# USB.net
KiCad netlist of a schematic drawn in EasyEDA Pro
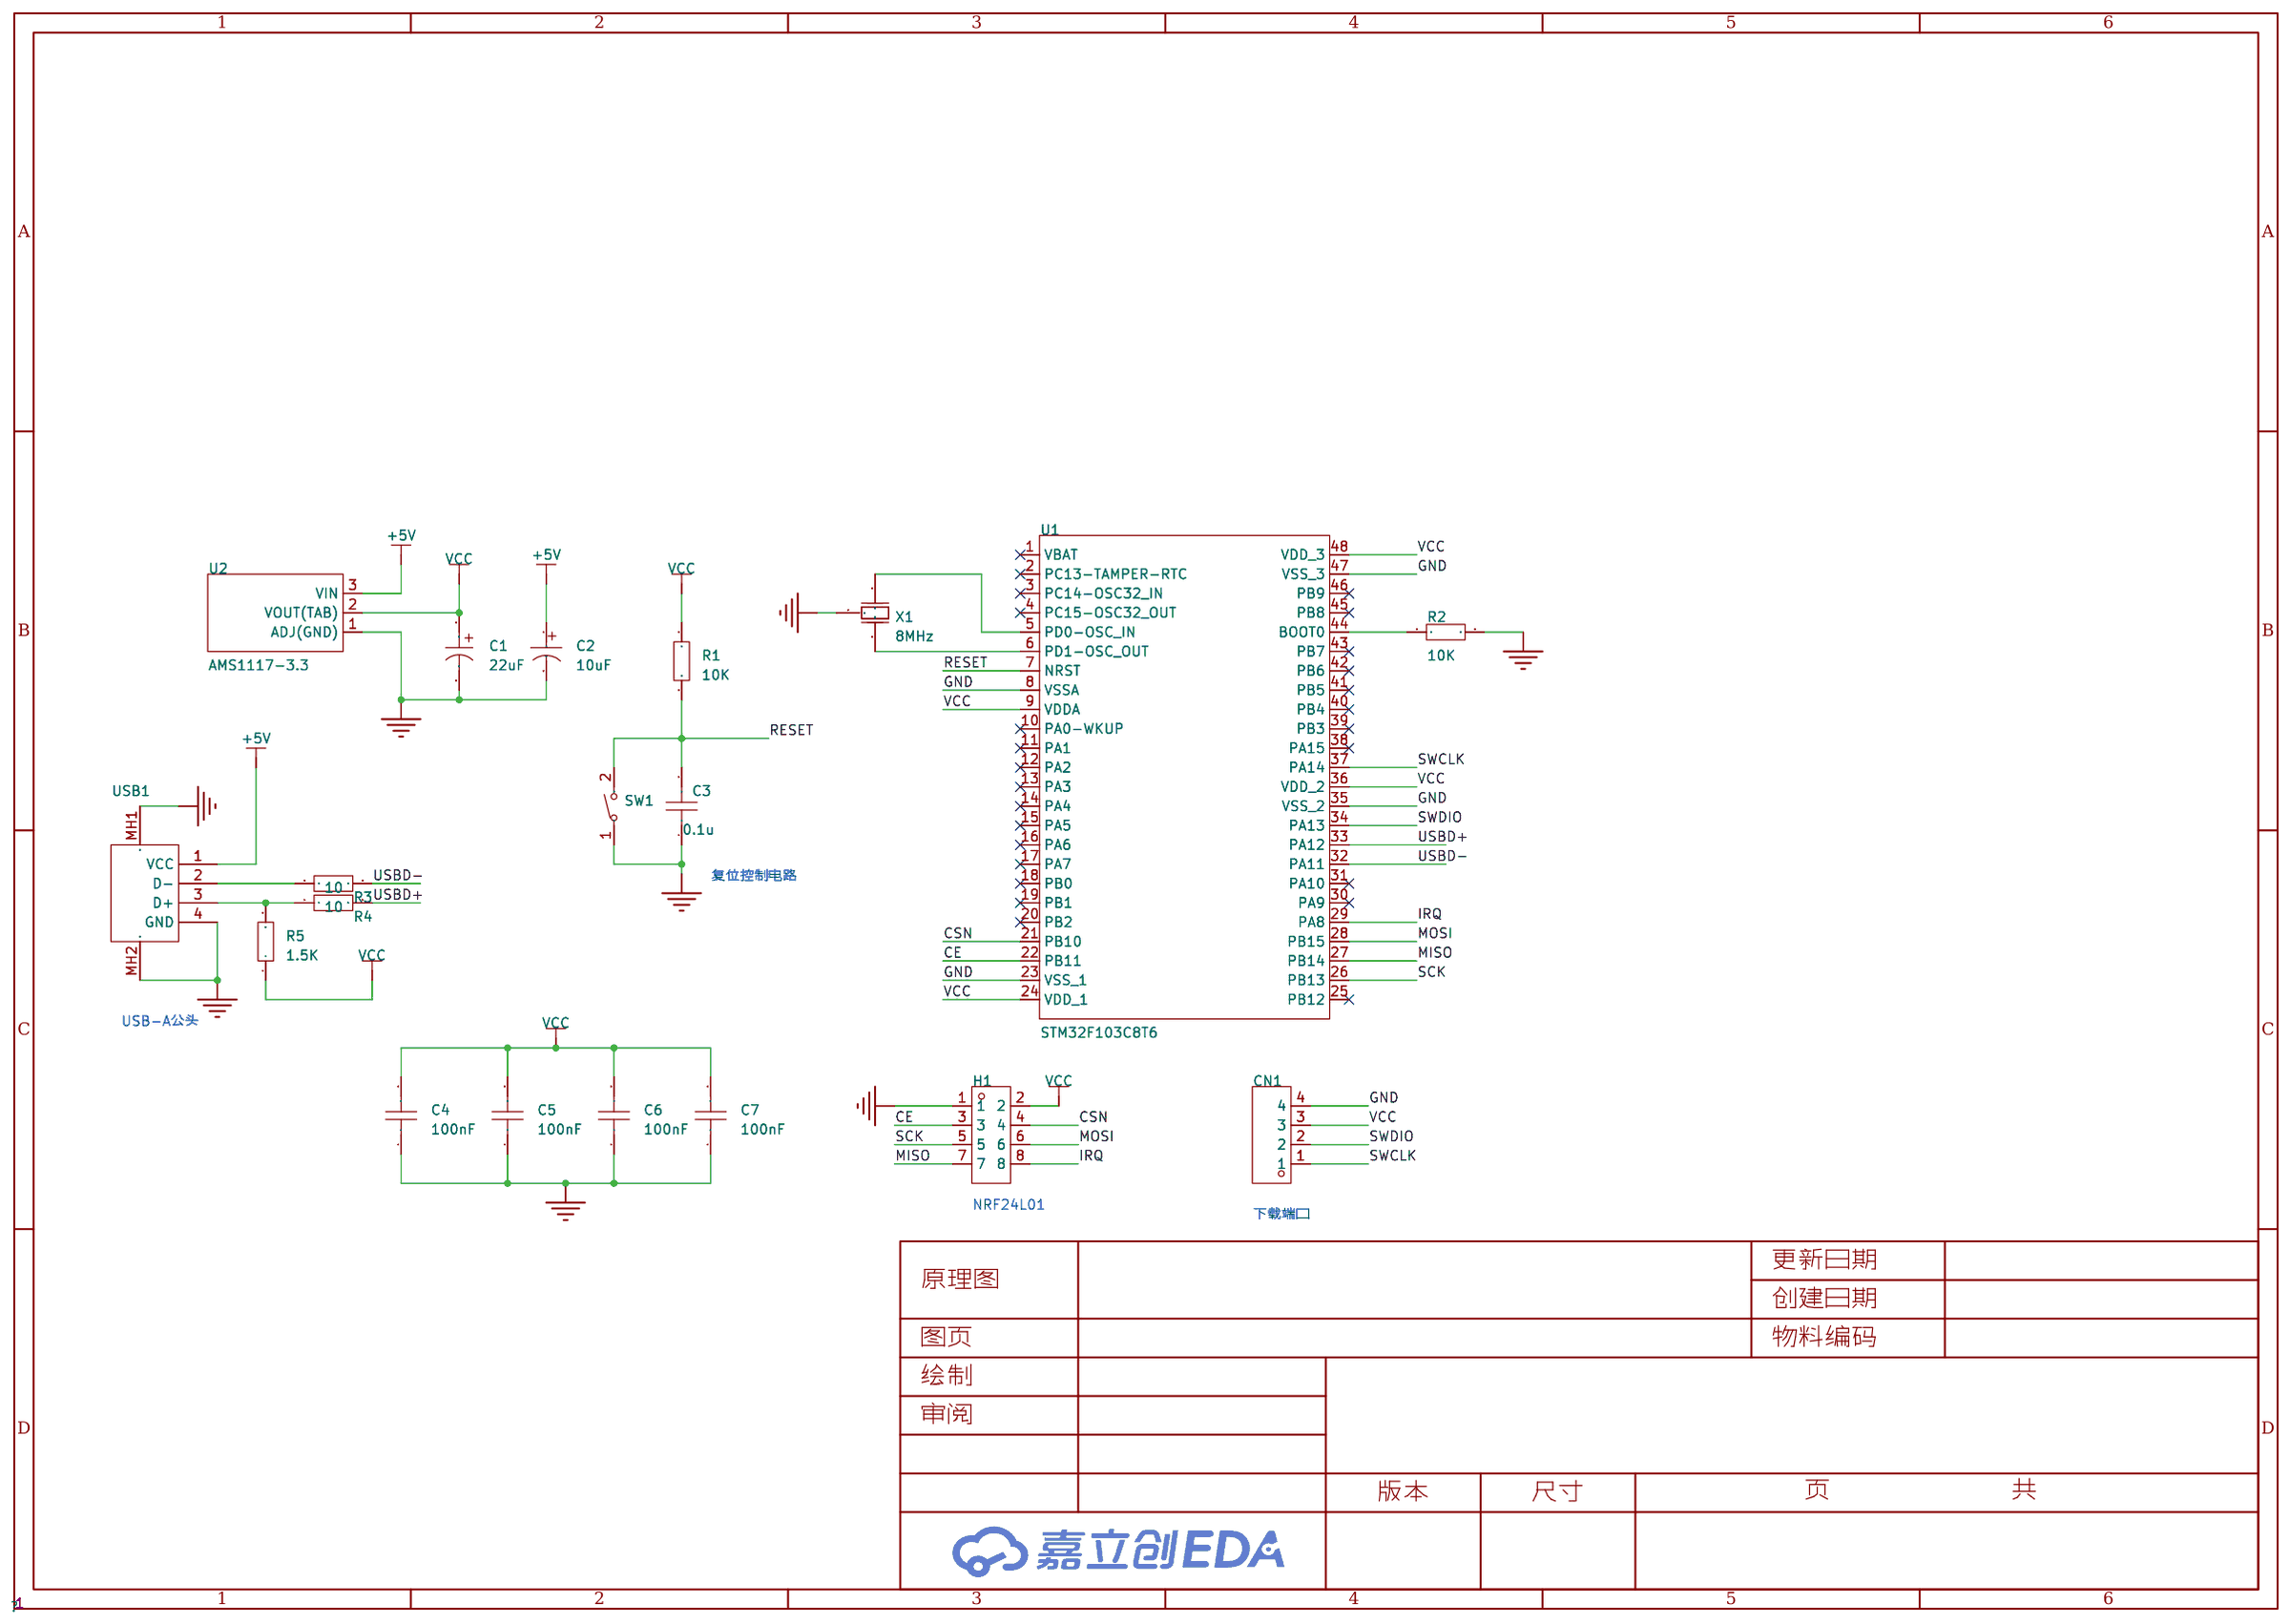
[diagram p0: schematic sheet]

(export (version "E")
  (design (tool "Eeschema 10.0.6"))
  (components
    (comp (ref "C1")
      (value "22uF")
      (footprint "easyedapro:CAP-SMD_BD5.0-L5.3-W5.3-LS6.0-FD")
      (description "容值:22uF;精度:±20%;额定电压:25V;纹波电流:25mA@120Hz;")
      (fields (field (name "Manufacturer Part") "CS1E220M-CRD54") (field (name "Manufacturer") "ROQANG(容强)"))
      (libsource (lib "easyedapro") (part "CS1E220M-CRD54_C3001207"))
    )
    (comp (ref "C2")
      (value "10uF")
      (footprint "easyedapro:CAP-SMD_BD4.0-L4.3-W4.3-FD")
      (description "容值:10uF;精度:±20%;额定电压:35V;纹波电流:15mA@120Hz;等效串联电阻(ESR):-;")
      (fields (field (name "Manufacturer Part") "RVT1V100M0405") (field (name "Manufacturer") "ROQANG(容强)"))
      (libsource (lib "easyedapro") (part "RVT1V100M0405-C72485"))
    )
    (comp (ref "C3")
      (value "0.1u")
      (footprint "easyedapro:C0603")
      (libsource (lib "easyedapro") (part "CapAcitance"))
    )
    (comp (ref "C4")
      (value "100nF")
      (footprint "easyedapro:C0603")
      (libsource (lib "easyedapro") (part "CapAcitance"))
    )
    (comp (ref "C5")
      (value "100nF")
      (footprint "easyedapro:C0603")
      (libsource (lib "easyedapro") (part "CapAcitance"))
    )
    (comp (ref "C6")
      (value "100nF")
      (footprint "easyedapro:C0603")
      (libsource (lib "easyedapro") (part "CapAcitance"))
    )
    (comp (ref "C7")
      (value "100nF")
      (footprint "easyedapro:C0603")
      (libsource (lib "easyedapro") (part "CapAcitance"))
    )
    (comp (ref "CN1")
      (value "HC-ZH1.5-4AW")
      (footprint "easyedapro:CONN-TH_4P-P1.50_HCTL_HC-ZH1.5-4AW")
      (fields (field (name "Manufacturer") "HCTL(华灿天禄)"))
      (libsource (lib "easyedapro") (part "HC-ZH1.5-4AW"))
    )
    (comp (ref "H1")
      (value "PM254V-12-08-H85")
      (footprint "easyedapro:HDR-TH_8P-P2.54-V-F-R2-C4-S2.54")
      (fields (field (name "Manufacturer") "XFCN(兴飞)"))
      (libsource (lib "easyedapro") (part "PM254V-12-08-H85_C2834799"))
    )
    (comp (ref "R1") (value "10K") (footprint "easyedapro:R0603") (libsource (lib "easyedapro") (part "电阻")))
    (comp (ref "R2") (value "10K") (footprint "easyedapro:R0603") (libsource (lib "easyedapro") (part "电阻")))
    (comp (ref "R3") (value "10") (footprint "easyedapro:R0603") (libsource (lib "easyedapro") (part "电阻")))
    (comp (ref "R4") (value "10") (footprint "easyedapro:R0603") (libsource (lib "easyedapro") (part "电阻")))
    (comp (ref "R5") (value "1.5K") (footprint "easyedapro:R0603") (libsource (lib "easyedapro") (part "电阻")))
    (comp (ref "SW1")
      (value "GT-TC060A-H025-L1S")
      (footprint "easyedapro:SW-SMD_L6.1-W3.5-LS8.0")
      (description "电路结构:单刀单掷;作用力:1.6N;安装方式:立贴;带支架:不带;触点电流:50mA;额定电压(AC):12V;额定电压(DC):12V;绝缘电阻:100MΩ;带灯:无;机械寿命:10万次;")
      (fields (field (name "Manufacturer") "G-Switch(品赞)"))
      (libsource (lib "easyedapro") (part "GT-TC060A-H025-L1S"))
    )
    (comp (ref "U1")
      (value "STM32F103C8T6")
      (footprint "easyedapro:LQFP-48_L7.0-W7.0-P0.50-LS9.0-BL")
      (description "CPU内核:ARM-M3;CPU最大主频:72MHz;应用领域:-;")
      (fields (field (name "Manufacturer") "ST(意法半导体)"))
      (libsource (lib "easyedapro") (part "STM32F103C8T6"))
    )
    (comp (ref "U2")
      (value "AMS1117-3.3")
      (footprint "easyedapro:SOT-89_L4.5-W2.5-P1.50-LS4.2-BR")
      (description "输出类型:固定;工作电压:18V;输出电压:3.3V;输出电流:1A;电源纹波抑制比(PSRR):60dB@(120Hz);输出极性:正极;")
      (fields (field (name "Manufacturer") "UMW(友台半导体)"))
      (libsource (lib "easyedapro") (part "AMS1117-3.3_C347256"))
    )
    (comp (ref "USB1")
      (value "AM90")
      (footprint "easyedapro:USB-AM-TH_AM90")
      (description "连接器类型:Type-A;标准:USB 2.0;公母:公;安装方式:弯插;触点数量:4P;端口数量:1;额定电流 - 电源:1.5A;工作温度范围:-25°C~+85°C;")
      (fields (field (name "Manufacturer") "SHOU HAN(首韩)"))
      (libsource (lib "easyedapro") (part "AM90"))
    )
    (comp (ref "X1")
      (value "8MHz")
      (footprint "easyedapro:OSC-SMD_3P-L3.2-W1.3-P1.2-L")
      (description "频率:8MHz;内置负载电容:33pF;谐振阻抗:40Ω;")
      (fields
        (field (name "Manufacturer Part") "CSTNE8M00G55A000R0")
        (field (name "Manufacturer") "muRata(村田)")
      )
      (libsource (lib "easyedapro") (part "CSTNE8M00G55A000R0"))
    )
  )
  (nets
    (net (code "1") (name "+5V") (class "Default")
      (node (ref "C2") (pin "1") (pinfunction "1_1") (pintype "input"))
      (node (ref "U2") (pin "3") (pinfunction "VIN_3") (pintype "unspecified"))
      (node (ref "USB1") (pin "1") (pinfunction "VCC_1") (pintype "input"))
    )
    (net (code "2") (name "/CE") (class "Default")
      (node (ref "H1") (pin "3") (pinfunction "3_3") (pintype "unspecified"))
      (node (ref "U1") (pin "22") (pinfunction "PB11_22") (pintype "unspecified"))
    )
    (net (code "3") (name "/CSN") (class "Default")
      (node (ref "H1") (pin "4") (pinfunction "4_4") (pintype "unspecified"))
      (node (ref "U1") (pin "21") (pinfunction "PB10_21") (pintype "unspecified"))
    )
    (net (code "4") (name "/IRQ") (class "Default")
      (node (ref "H1") (pin "8") (pinfunction "8_8") (pintype "unspecified"))
      (node (ref "U1") (pin "29") (pinfunction "PA8_29") (pintype "unspecified"))
    )
    (net (code "5") (name "/MISO") (class "Default")
      (node (ref "H1") (pin "7") (pinfunction "7_7") (pintype "unspecified"))
      (node (ref "U1") (pin "27") (pinfunction "PB14_27") (pintype "unspecified"))
    )
    (net (code "6") (name "/MOSI") (class "Default")
      (node (ref "H1") (pin "6") (pinfunction "6_6") (pintype "unspecified"))
      (node (ref "U1") (pin "28") (pinfunction "PB15_28") (pintype "unspecified"))
    )
    (net (code "7") (name "/RESET") (class "Default")
      (node (ref "C3") (pin "2") (pinfunction "2_2") (pintype "input"))
      (node (ref "R1") (pin "2") (pinfunction "2_2") (pintype "input"))
      (node (ref "SW1") (pin "2") (pinfunction "2_2") (pintype "unspecified"))
      (node (ref "U1") (pin "7") (pinfunction "NRST_7") (pintype "unspecified"))
    )
    (net (code "8") (name "/SCK") (class "Default")
      (node (ref "H1") (pin "5") (pinfunction "5_5") (pintype "unspecified"))
      (node (ref "U1") (pin "26") (pinfunction "PB13_26") (pintype "unspecified"))
    )
    (net (code "9") (name "/SWCLK") (class "Default")
      (node (ref "CN1") (pin "1") (pinfunction "1_1") (pintype "unspecified"))
      (node (ref "U1") (pin "37") (pinfunction "PA14_37") (pintype "unspecified"))
    )
    (net (code "10") (name "/SWDIO") (class "Default")
      (node (ref "CN1") (pin "2") (pinfunction "2_2") (pintype "unspecified"))
      (node (ref "U1") (pin "34") (pinfunction "PA13_34") (pintype "unspecified"))
    )
    (net (code "11") (name "/USBD+") (class "Default")
      (node (ref "R4") (pin "2") (pinfunction "2_2") (pintype "input"))
      (node (ref "U1") (pin "33") (pinfunction "PA12_33") (pintype "unspecified"))
    )
    (net (code "12") (name "/USBD-") (class "Default")
      (node (ref "R3") (pin "2") (pinfunction "2_2") (pintype "input"))
      (node (ref "U1") (pin "32") (pinfunction "PA11_32") (pintype "unspecified"))
    )
    (net (code "13") (name "GND") (class "Default")
      (node (ref "C1") (pin "2") (pinfunction "2_2") (pintype "input"))
      (node (ref "C2") (pin "2") (pinfunction "2_2") (pintype "input"))
      (node (ref "C3") (pin "1") (pinfunction "1_1") (pintype "input"))
      (node (ref "C4") (pin "1") (pinfunction "1_1") (pintype "input"))
      (node (ref "C5") (pin "1") (pinfunction "1_1") (pintype "input"))
      (node (ref "C6") (pin "1") (pinfunction "1_1") (pintype "input"))
      (node (ref "C7") (pin "1") (pinfunction "1_1") (pintype "input"))
      (node (ref "CN1") (pin "4") (pinfunction "4_4") (pintype "unspecified"))
      (node (ref "H1") (pin "1") (pinfunction "1_1") (pintype "unspecified"))
      (node (ref "R2") (pin "2") (pinfunction "2_2") (pintype "input"))
      (node (ref "SW1") (pin "1") (pinfunction "1_1") (pintype "unspecified"))
      (node (ref "U1") (pin "23") (pinfunction "VSS_1_23") (pintype "unspecified"))
      (node (ref "U1") (pin "35") (pinfunction "VSS_2_35") (pintype "unspecified"))
      (node (ref "U1") (pin "47") (pinfunction "VSS_3_47") (pintype "unspecified"))
      (node (ref "U1") (pin "8") (pinfunction "VSSA_8") (pintype "unspecified"))
      (node (ref "U2") (pin "1") (pinfunction "ADJ(GND)_1") (pintype "unspecified"))
      (node (ref "USB1") (pin "4") (pinfunction "GND_4") (pintype "input"))
      (node (ref "USB1") (pin "MH1") (pinfunction "MH1_MH1") (pintype "unspecified"))
      (node (ref "USB1") (pin "MH2") (pinfunction "MH2_MH2") (pintype "unspecified"))
      (node (ref "X1") (pin "2") (pinfunction "GND_2") (pintype "input"))
    )
    (net (code "14") (name "Net-(U1-BOOT0)") (class "Default")
      (node (ref "R2") (pin "1") (pinfunction "1_1") (pintype "input"))
      (node (ref "U1") (pin "44") (pinfunction "BOOT0_44") (pintype "unspecified"))
    )
    (net (code "15") (name "Net-(U1-PD0-OSC_IN)") (class "Default")
      (node (ref "U1") (pin "5") (pinfunction "PD0-OSC_IN_5") (pintype "unspecified"))
      (node (ref "X1") (pin "3") (pinfunction "OSC2_3") (pintype "input"))
    )
    (net (code "16") (name "Net-(U1-PD1-OSC_OUT)") (class "Default")
      (node (ref "U1") (pin "6") (pinfunction "PD1-OSC_OUT_6") (pintype "unspecified"))
      (node (ref "X1") (pin "1") (pinfunction "OSC1_1") (pintype "input"))
    )
    (net (code "17") (name "Net-(USB1-D+)") (class "Default")
      (node (ref "R4") (pin "1") (pinfunction "1_1") (pintype "input"))
      (node (ref "R5") (pin "2") (pinfunction "2_2") (pintype "input"))
      (node (ref "USB1") (pin "3") (pinfunction "D+_3") (pintype "input"))
    )
    (net (code "18") (name "Net-(USB1-D-)") (class "Default")
      (node (ref "R3") (pin "1") (pinfunction "1_1") (pintype "input"))
      (node (ref "USB1") (pin "2") (pinfunction "D-_2") (pintype "input"))
    )
    (net (code "19") (name "VCC") (class "Default")
      (node (ref "C1") (pin "1") (pinfunction "1_1") (pintype "input"))
      (node (ref "C4") (pin "2") (pinfunction "2_2") (pintype "input"))
      (node (ref "C5") (pin "2") (pinfunction "2_2") (pintype "input"))
      (node (ref "C6") (pin "2") (pinfunction "2_2") (pintype "input"))
      (node (ref "C7") (pin "2") (pinfunction "2_2") (pintype "input"))
      (node (ref "CN1") (pin "3") (pinfunction "3_3") (pintype "unspecified"))
      (node (ref "H1") (pin "2") (pinfunction "2_2") (pintype "unspecified"))
      (node (ref "R1") (pin "1") (pinfunction "1_1") (pintype "input"))
      (node (ref "R5") (pin "1") (pinfunction "1_1") (pintype "input"))
      (node (ref "U1") (pin "24") (pinfunction "VDD_1_24") (pintype "unspecified"))
      (node (ref "U1") (pin "36") (pinfunction "VDD_2_36") (pintype "unspecified"))
      (node (ref "U1") (pin "48") (pinfunction "VDD_3_48") (pintype "unspecified"))
      (node (ref "U1") (pin "9") (pinfunction "VDDA_9") (pintype "unspecified"))
      (node (ref "U2") (pin "2") (pinfunction "VOUT(TAB)_2") (pintype "unspecified"))
    )
    (net (code "20") (name "unconnected-(U1-PA0-WKUP-Pad10)") (class "Default")
      (node (ref "U1") (pin "10") (pinfunction "PA0-WKUP_10") (pintype "unspecified+no_connect"))
    )
    (net (code "21") (name "unconnected-(U1-PA1-Pad11)") (class "Default")
      (node (ref "U1") (pin "11") (pinfunction "PA1_11") (pintype "unspecified+no_connect"))
    )
    (net (code "22") (name "unconnected-(U1-PA2-Pad12)") (class "Default")
      (node (ref "U1") (pin "12") (pinfunction "PA2_12") (pintype "unspecified+no_connect"))
    )
    (net (code "23") (name "unconnected-(U1-PA3-Pad13)") (class "Default")
      (node (ref "U1") (pin "13") (pinfunction "PA3_13") (pintype "unspecified+no_connect"))
    )
    (net (code "24") (name "unconnected-(U1-PA4-Pad14)") (class "Default")
      (node (ref "U1") (pin "14") (pinfunction "PA4_14") (pintype "unspecified+no_connect"))
    )
    (net (code "25") (name "unconnected-(U1-PA5-Pad15)") (class "Default")
      (node (ref "U1") (pin "15") (pinfunction "PA5_15") (pintype "unspecified+no_connect"))
    )
    (net (code "26") (name "unconnected-(U1-PA6-Pad16)") (class "Default")
      (node (ref "U1") (pin "16") (pinfunction "PA6_16") (pintype "unspecified+no_connect"))
    )
    (net (code "27") (name "unconnected-(U1-PA7-Pad17)") (class "Default")
      (node (ref "U1") (pin "17") (pinfunction "PA7_17") (pintype "unspecified+no_connect"))
    )
    (net (code "28") (name "unconnected-(U1-PA9-Pad30)") (class "Default")
      (node (ref "U1") (pin "30") (pinfunction "PA9_30") (pintype "unspecified+no_connect"))
    )
    (net (code "29") (name "unconnected-(U1-PA10-Pad31)") (class "Default")
      (node (ref "U1") (pin "31") (pinfunction "PA10_31") (pintype "unspecified+no_connect"))
    )
    (net (code "30") (name "unconnected-(U1-PA15-Pad38)") (class "Default")
      (node (ref "U1") (pin "38") (pinfunction "PA15_38") (pintype "unspecified+no_connect"))
    )
    (net (code "31") (name "unconnected-(U1-PB0-Pad18)") (class "Default")
      (node (ref "U1") (pin "18") (pinfunction "PB0_18") (pintype "unspecified+no_connect"))
    )
    (net (code "32") (name "unconnected-(U1-PB1-Pad19)") (class "Default")
      (node (ref "U1") (pin "19") (pinfunction "PB1_19") (pintype "unspecified+no_connect"))
    )
    (net (code "33") (name "unconnected-(U1-PB2-Pad20)") (class "Default")
      (node (ref "U1") (pin "20") (pinfunction "PB2_20") (pintype "unspecified+no_connect"))
    )
    (net (code "34") (name "unconnected-(U1-PB3-Pad39)") (class "Default")
      (node (ref "U1") (pin "39") (pinfunction "PB3_39") (pintype "unspecified+no_connect"))
    )
    (net (code "35") (name "unconnected-(U1-PB4-Pad40)") (class "Default")
      (node (ref "U1") (pin "40") (pinfunction "PB4_40") (pintype "unspecified+no_connect"))
    )
    (net (code "36") (name "unconnected-(U1-PB5-Pad41)") (class "Default")
      (node (ref "U1") (pin "41") (pinfunction "PB5_41") (pintype "unspecified+no_connect"))
    )
    (net (code "37") (name "unconnected-(U1-PB6-Pad42)") (class "Default")
      (node (ref "U1") (pin "42") (pinfunction "PB6_42") (pintype "unspecified+no_connect"))
    )
    (net (code "38") (name "unconnected-(U1-PB7-Pad43)") (class "Default")
      (node (ref "U1") (pin "43") (pinfunction "PB7_43") (pintype "unspecified+no_connect"))
    )
    (net (code "39") (name "unconnected-(U1-PB8-Pad45)") (class "Default")
      (node (ref "U1") (pin "45") (pinfunction "PB8_45") (pintype "unspecified+no_connect"))
    )
    (net (code "40") (name "unconnected-(U1-PB9-Pad46)") (class "Default")
      (node (ref "U1") (pin "46") (pinfunction "PB9_46") (pintype "unspecified+no_connect"))
    )
    (net (code "41") (name "unconnected-(U1-PB12-Pad25)") (class "Default")
      (node (ref "U1") (pin "25") (pinfunction "PB12_25") (pintype "unspecified+no_connect"))
    )
    (net (code "42") (name "unconnected-(U1-PC13-TAMPER-RTC-Pad2)") (class "Default")
      (node (ref "U1") (pin "2") (pinfunction "PC13-TAMPER-RTC_2") (pintype "unspecified+no_connect"))
    )
    (net (code "43") (name "unconnected-(U1-PC14-OSC32_IN-Pad3)") (class "Default")
      (node (ref "U1") (pin "3") (pinfunction "PC14-OSC32_IN_3") (pintype "unspecified+no_connect"))
    )
    (net (code "44") (name "unconnected-(U1-PC15-OSC32_OUT-Pad4)") (class "Default")
      (node (ref "U1") (pin "4") (pinfunction "PC15-OSC32_OUT_4") (pintype "unspecified+no_connect"))
    )
    (net (code "45") (name "unconnected-(U1-VBAT-Pad1)") (class "Default")
      (node (ref "U1") (pin "1") (pinfunction "VBAT_1") (pintype "unspecified+no_connect"))
    )
  )
)
